# keyboard.net
KiCad netlist of a schematic drawn in Altium Designer
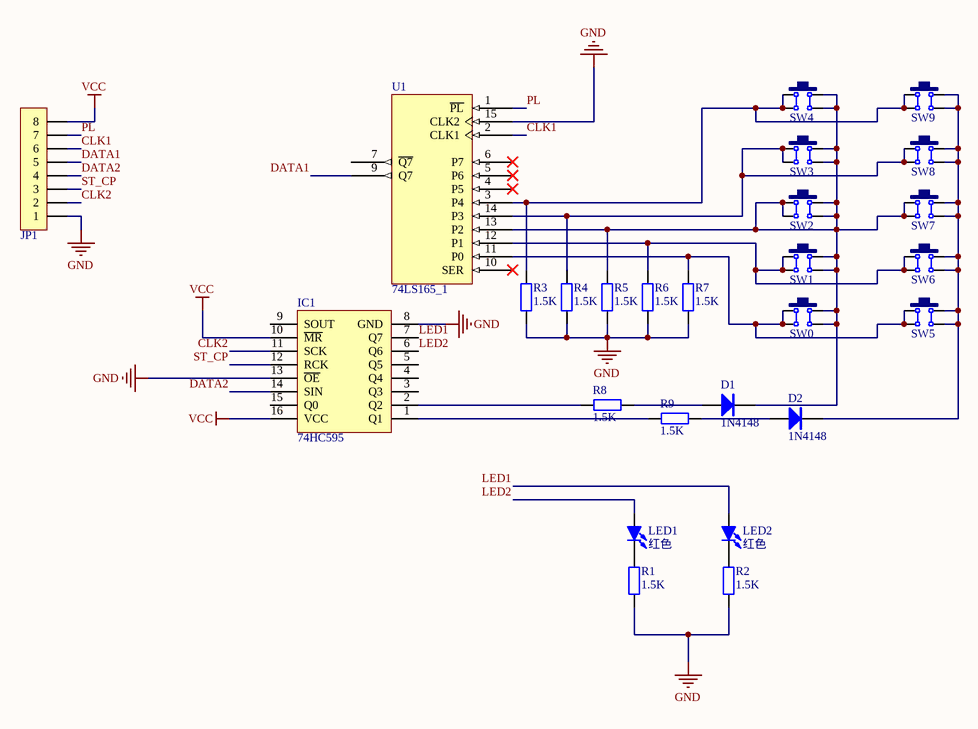
[diagram p0: keyboard.SchDoc]

(export (version "E")
  (design (tool "Eeschema 10.0.6"))
  (components
    (comp (ref "D1")
      (value "1N4148")
      (footprint "SOD-323")
      (description "高速开关二极管")
      (fields (field (name "版权归属") "源创客"))
      (libsource (lib "8.1   - 二极管-整流桥") (part "1N4148"))
    )
    (comp (ref "D2")
      (value "1N4148")
      (footprint "SOD-323")
      (description "高速开关二极管")
      (fields (field (name "版权归属") "源创客"))
      (libsource (lib "8.1   - 二极管-整流桥") (part "1N4148"))
    )
    (comp (ref "IC1")
      (value "74HC595")
      (footprint "SOP16_N")
      (description "8位移位寄存器")
      (fields (field (name "版权归属") "源创客"))
      (libsource (lib "1.2   - 74系列芯片") (part "74HC595"))
    )
    (comp (ref "JP1")
      (value "HDR-1X8")
      (footprint "XH2.54-WI-8P")
      (description "8P接插件")
      (fields (field (name "版权归属") "源创客"))
      (libsource (lib "4.5   - 接插件-脚距2.54") (part "Header 8"))
    )
    (comp (ref "LED1")
      (value "红色")
      (footprint "LED 0805R")
      (description "插件LED")
      (fields (field (name "版权归属") "源创客"))
      (libsource (lib "9.1   - LED") (part "LED-3MM"))
    )
    (comp (ref "LED2")
      (value "红色")
      (footprint "LED 0805R")
      (description "插件LED")
      (fields (field (name "版权归属") "源创客"))
      (libsource (lib "9.1   - LED") (part "LED-3MM"))
    )
    (comp (ref "R1")
      (value "1.5K")
      (footprint "R 0805_L")
      (description "贴片电阻")
      (fields (field (name "版权归属") "源创客"))
      (libsource (lib "3.1   - 电阻-电容-电感") (part "R"))
    )
    (comp (ref "R2")
      (value "1.5K")
      (footprint "R 0805_L")
      (description "贴片电阻")
      (fields (field (name "版权归属") "源创客"))
      (libsource (lib "3.1   - 电阻-电容-电感") (part "R"))
    )
    (comp (ref "R3")
      (value "1.5K")
      (footprint "R 0805_L")
      (description "贴片电阻")
      (fields (field (name "版权归属") "源创客"))
      (libsource (lib "3.1   - 电阻-电容-电感") (part "R"))
    )
    (comp (ref "R4")
      (value "1.5K")
      (footprint "R 0805_L")
      (description "贴片电阻")
      (fields (field (name "版权归属") "源创客"))
      (libsource (lib "3.1   - 电阻-电容-电感") (part "R"))
    )
    (comp (ref "R5")
      (value "1.5K")
      (footprint "R 0805_L")
      (description "贴片电阻")
      (fields (field (name "版权归属") "源创客"))
      (libsource (lib "3.1   - 电阻-电容-电感") (part "R"))
    )
    (comp (ref "R6")
      (value "1.5K")
      (footprint "R 0805_L")
      (description "贴片电阻")
      (fields (field (name "版权归属") "源创客"))
      (libsource (lib "3.1   - 电阻-电容-电感") (part "R"))
    )
    (comp (ref "R7")
      (value "1.5K")
      (footprint "R 0805_L")
      (description "贴片电阻")
      (fields (field (name "版权归属") "源创客"))
      (libsource (lib "3.1   - 电阻-电容-电感") (part "R"))
    )
    (comp (ref "R8")
      (value "1.5K")
      (footprint "R 0805_L")
      (description "贴片电阻")
      (fields (field (name "版权归属") "源创客"))
      (libsource (lib "3.1   - 电阻-电容-电感") (part "R"))
    )
    (comp (ref "R9")
      (value "1.5K")
      (footprint "R 0805_L")
      (description "贴片电阻")
      (fields (field (name "版权归属") "源创客"))
      (libsource (lib "3.1   - 电阻-电容-电感") (part "R"))
    )
    (comp (ref "SW0")
      (value "12x12x5")
      (footprint "TSW SMD-12*12*4.3")
      (description "贴片12x12轻触开关")
      (fields (field (name "版权归属") "源创客"))
      (libsource (lib "5.1   - 按键-开关") (part "TSW SMD-12x12"))
    )
    (comp (ref "SW1")
      (value "12x12x5")
      (footprint "TSW SMD-12*12*4.3")
      (description "贴片12x12轻触开关")
      (fields (field (name "版权归属") "源创客"))
      (libsource (lib "5.1   - 按键-开关") (part "TSW SMD-12x12"))
    )
    (comp (ref "SW2")
      (value "12x12x5")
      (footprint "TSW SMD-12*12*4.3")
      (description "贴片12x12轻触开关")
      (fields (field (name "版权归属") "源创客"))
      (libsource (lib "5.1   - 按键-开关") (part "TSW SMD-12x12"))
    )
    (comp (ref "SW3")
      (value "12x12x5")
      (footprint "TSW SMD-12*12*4.3")
      (description "贴片12x12轻触开关")
      (fields (field (name "版权归属") "源创客"))
      (libsource (lib "5.1   - 按键-开关") (part "TSW SMD-12x12"))
    )
    (comp (ref "SW4")
      (value "12x12x5")
      (footprint "TSW SMD-12*12*4.3")
      (description "贴片12x12轻触开关")
      (fields (field (name "版权归属") "源创客"))
      (libsource (lib "5.1   - 按键-开关") (part "TSW SMD-12x12"))
    )
    (comp (ref "SW5")
      (value "12x12x5")
      (footprint "TSW SMD-12*12*4.3")
      (description "贴片12x12轻触开关")
      (fields (field (name "版权归属") "源创客"))
      (libsource (lib "5.1   - 按键-开关") (part "TSW SMD-12x12"))
    )
    (comp (ref "SW6")
      (value "12x12x5")
      (footprint "TSW SMD-12*12*4.3")
      (description "贴片12x12轻触开关")
      (fields (field (name "版权归属") "源创客"))
      (libsource (lib "5.1   - 按键-开关") (part "TSW SMD-12x12"))
    )
    (comp (ref "SW7")
      (value "12x12x5")
      (footprint "TSW SMD-12*12*4.3")
      (description "贴片12x12轻触开关")
      (fields (field (name "版权归属") "源创客"))
      (libsource (lib "5.1   - 按键-开关") (part "TSW SMD-12x12"))
    )
    (comp (ref "SW8")
      (value "12x12x5")
      (footprint "TSW SMD-12*12*4.3")
      (description "贴片12x12轻触开关")
      (fields (field (name "版权归属") "源创客"))
      (libsource (lib "5.1   - 按键-开关") (part "TSW SMD-12x12"))
    )
    (comp (ref "SW9")
      (value "12x12x5")
      (footprint "TSW SMD-12*12*4.3")
      (description "贴片12x12轻触开关")
      (fields (field (name "版权归属") "源创客"))
      (libsource (lib "5.1   - 按键-开关") (part "TSW SMD-12x12"))
    )
    (comp (ref "U1") (value "74LS165_1") (footprint "SOP16_M") (libsource (lib "常用器件") (part "74LS165_1")))
  )
  (nets
    (net (code "1") (name "/CLK1") (class "Default")
      (node (ref "JP1") (pin "6") (pinfunction "6_6") (pintype "passive"))
      (node (ref "U1") (pin "2") (pinfunction "CLK1_2") (pintype "input"))
    )
    (net (code "2") (name "/CLK2") (class "Default")
      (node (ref "IC1") (pin "11") (pinfunction "SCK_11") (pintype "passive"))
      (node (ref "JP1") (pin "2") (pinfunction "2_2") (pintype "passive"))
    )
    (net (code "3") (name "/DATA1") (class "Default")
      (node (ref "JP1") (pin "5") (pinfunction "5_5") (pintype "passive"))
      (node (ref "U1") (pin "9") (pinfunction "Q7_9") (pintype "output"))
    )
    (net (code "4") (name "/DATA2") (class "Default")
      (node (ref "IC1") (pin "14") (pinfunction "SIN_14") (pintype "passive"))
      (node (ref "JP1") (pin "4") (pinfunction "4_4") (pintype "passive"))
    )
    (net (code "5") (name "/LED1") (class "Default")
      (node (ref "IC1") (pin "7") (pinfunction "Q7_7") (pintype "passive"))
      (node (ref "LED2") (pin "1") (pinfunction "A_1") (pintype "passive"))
    )
    (net (code "6") (name "/LED2") (class "Default")
      (node (ref "IC1") (pin "6") (pinfunction "Q6_6") (pintype "passive"))
      (node (ref "LED1") (pin "1") (pinfunction "A_1") (pintype "passive"))
    )
    (net (code "7") (name "/PL") (class "Default")
      (node (ref "JP1") (pin "7") (pinfunction "7_7") (pintype "passive"))
      (node (ref "U1") (pin "1") (pinfunction "~{PL}_1") (pintype "input"))
    )
    (net (code "8") (name "/ST_CP") (class "Default")
      (node (ref "IC1") (pin "12") (pinfunction "RCK_12") (pintype "passive"))
      (node (ref "JP1") (pin "3") (pinfunction "3_3") (pintype "passive"))
    )
    (net (code "9") (name "GND") (class "Default")
      (node (ref "IC1") (pin "13") (pinfunction "~{OE}_13") (pintype "passive"))
      (node (ref "IC1") (pin "8") (pinfunction "GND_8") (pintype "passive"))
      (node (ref "JP1") (pin "1") (pinfunction "1_1") (pintype "passive"))
      (node (ref "R1") (pin "2") (pinfunction "2_2") (pintype "passive"))
      (node (ref "R2") (pin "2") (pinfunction "2_2") (pintype "passive"))
      (node (ref "R3") (pin "2") (pinfunction "2_2") (pintype "passive"))
      (node (ref "R4") (pin "2") (pinfunction "2_2") (pintype "passive"))
      (node (ref "R5") (pin "2") (pinfunction "2_2") (pintype "passive"))
      (node (ref "R6") (pin "2") (pinfunction "2_2") (pintype "passive"))
      (node (ref "R7") (pin "2") (pinfunction "2_2") (pintype "passive"))
      (node (ref "U1") (pin "15") (pinfunction "CLK2_15") (pintype "input"))
      (node (ref "U1") (pin "8") (pinfunction "GND_8") (pintype "power_in"))
    )
    (net (code "10") (name "Net-(D1-A)") (class "Default")
      (node (ref "D1") (pin "1") (pinfunction "A_1") (pintype "passive"))
      (node (ref "R8") (pin "2") (pinfunction "2_2") (pintype "passive"))
    )
    (net (code "11") (name "Net-(D1-K)") (class "Default")
      (node (ref "D1") (pin "2") (pinfunction "K_2") (pintype "passive"))
      (node (ref "R5") (pin "1") (pinfunction "1_1") (pintype "passive"))
      (node (ref "SW0") (pin "2") (pinfunction "2_2") (pintype "passive"))
      (node (ref "SW0") (pin "3") (pinfunction "3_3") (pintype "passive"))
      (node (ref "SW1") (pin "2") (pinfunction "2_2") (pintype "passive"))
      (node (ref "SW1") (pin "3") (pinfunction "3_3") (pintype "passive"))
      (node (ref "SW2") (pin "1") (pinfunction "1_1") (pintype "passive"))
      (node (ref "SW2") (pin "2") (pinfunction "2_2") (pintype "passive"))
      (node (ref "SW2") (pin "3") (pinfunction "3_3") (pintype "passive"))
      (node (ref "SW2") (pin "4") (pinfunction "4_4") (pintype "passive"))
      (node (ref "SW3") (pin "2") (pinfunction "2_2") (pintype "passive"))
      (node (ref "SW3") (pin "3") (pinfunction "3_3") (pintype "passive"))
      (node (ref "SW4") (pin "2") (pinfunction "2_2") (pintype "passive"))
      (node (ref "SW4") (pin "3") (pinfunction "3_3") (pintype "passive"))
      (node (ref "SW7") (pin "1") (pinfunction "1_1") (pintype "passive"))
      (node (ref "SW7") (pin "4") (pinfunction "4_4") (pintype "passive"))
      (node (ref "U1") (pin "13") (pinfunction "P2_13") (pintype "input"))
    )
    (net (code "12") (name "Net-(D2-A)") (class "Default")
      (node (ref "D2") (pin "1") (pinfunction "A_1") (pintype "passive"))
      (node (ref "R9") (pin "2") (pinfunction "2_2") (pintype "passive"))
    )
    (net (code "13") (name "Net-(D2-K)") (class "Default")
      (node (ref "D2") (pin "2") (pinfunction "K_2") (pintype "passive"))
      (node (ref "SW5") (pin "2") (pinfunction "2_2") (pintype "passive"))
      (node (ref "SW5") (pin "3") (pinfunction "3_3") (pintype "passive"))
      (node (ref "SW6") (pin "2") (pinfunction "2_2") (pintype "passive"))
      (node (ref "SW6") (pin "3") (pinfunction "3_3") (pintype "passive"))
      (node (ref "SW7") (pin "2") (pinfunction "2_2") (pintype "passive"))
      (node (ref "SW7") (pin "3") (pinfunction "3_3") (pintype "passive"))
      (node (ref "SW8") (pin "2") (pinfunction "2_2") (pintype "passive"))
      (node (ref "SW8") (pin "3") (pinfunction "3_3") (pintype "passive"))
      (node (ref "SW9") (pin "2") (pinfunction "2_2") (pintype "passive"))
      (node (ref "SW9") (pin "3") (pinfunction "3_3") (pintype "passive"))
    )
    (net (code "14") (name "Net-(IC1-Q1)") (class "Default")
      (node (ref "IC1") (pin "1") (pinfunction "Q1_1") (pintype "passive"))
      (node (ref "R9") (pin "1") (pinfunction "1_1") (pintype "passive"))
    )
    (net (code "15") (name "Net-(IC1-Q2)") (class "Default")
      (node (ref "IC1") (pin "2") (pinfunction "Q2_2") (pintype "passive"))
      (node (ref "R8") (pin "1") (pinfunction "1_1") (pintype "passive"))
    )
    (net (code "16") (name "Net-(LED1-K)") (class "Default")
      (node (ref "LED1") (pin "2") (pinfunction "K_2") (pintype "passive"))
      (node (ref "R1") (pin "1") (pinfunction "1_1") (pintype "passive"))
    )
    (net (code "17") (name "Net-(LED2-K)") (class "Default")
      (node (ref "LED2") (pin "2") (pinfunction "K_2") (pintype "passive"))
      (node (ref "R2") (pin "1") (pinfunction "1_1") (pintype "passive"))
    )
    (net (code "18") (name "Net-(U1-P0)") (class "Default")
      (node (ref "R7") (pin "1") (pinfunction "1_1") (pintype "passive"))
      (node (ref "SW0") (pin "1") (pinfunction "1_1") (pintype "passive"))
      (node (ref "SW0") (pin "4") (pinfunction "4_4") (pintype "passive"))
      (node (ref "SW5") (pin "1") (pinfunction "1_1") (pintype "passive"))
      (node (ref "SW5") (pin "4") (pinfunction "4_4") (pintype "passive"))
      (node (ref "U1") (pin "11") (pinfunction "P0_11") (pintype "input"))
    )
    (net (code "19") (name "Net-(U1-P1)") (class "Default")
      (node (ref "R6") (pin "1") (pinfunction "1_1") (pintype "passive"))
      (node (ref "SW1") (pin "1") (pinfunction "1_1") (pintype "passive"))
      (node (ref "SW1") (pin "4") (pinfunction "4_4") (pintype "passive"))
      (node (ref "SW6") (pin "1") (pinfunction "1_1") (pintype "passive"))
      (node (ref "SW6") (pin "4") (pinfunction "4_4") (pintype "passive"))
      (node (ref "U1") (pin "12") (pinfunction "P1_12") (pintype "input"))
    )
    (net (code "20") (name "Net-(U1-P3)") (class "Default")
      (node (ref "R4") (pin "1") (pinfunction "1_1") (pintype "passive"))
      (node (ref "SW3") (pin "1") (pinfunction "1_1") (pintype "passive"))
      (node (ref "SW3") (pin "4") (pinfunction "4_4") (pintype "passive"))
      (node (ref "SW8") (pin "1") (pinfunction "1_1") (pintype "passive"))
      (node (ref "SW8") (pin "4") (pinfunction "4_4") (pintype "passive"))
      (node (ref "U1") (pin "14") (pinfunction "P3_14") (pintype "input"))
    )
    (net (code "21") (name "Net-(U1-P4)") (class "Default")
      (node (ref "R3") (pin "1") (pinfunction "1_1") (pintype "passive"))
      (node (ref "SW4") (pin "1") (pinfunction "1_1") (pintype "passive"))
      (node (ref "SW4") (pin "4") (pinfunction "4_4") (pintype "passive"))
      (node (ref "SW9") (pin "1") (pinfunction "1_1") (pintype "passive"))
      (node (ref "SW9") (pin "4") (pinfunction "4_4") (pintype "passive"))
      (node (ref "U1") (pin "3") (pinfunction "P4_3") (pintype "input"))
    )
    (net (code "22") (name "VCC") (class "Default")
      (node (ref "IC1") (pin "10") (pinfunction "~{MR}_10") (pintype "passive"))
      (node (ref "IC1") (pin "16") (pinfunction "VCC_16") (pintype "passive"))
      (node (ref "JP1") (pin "8") (pinfunction "8_8") (pintype "passive"))
      (node (ref "U1") (pin "16") (pinfunction "VCC_16") (pintype "power_in"))
    )
    (net (code "23") (name "unconnected-(IC1-Q0-Pad15)") (class "Default")
      (node (ref "IC1") (pin "15") (pinfunction "Q0_15") (pintype "passive"))
    )
    (net (code "24") (name "unconnected-(IC1-Q3-Pad3)") (class "Default")
      (node (ref "IC1") (pin "3") (pinfunction "Q3_3") (pintype "passive"))
    )
    (net (code "25") (name "unconnected-(IC1-Q4-Pad4)") (class "Default")
      (node (ref "IC1") (pin "4") (pinfunction "Q4_4") (pintype "passive"))
    )
    (net (code "26") (name "unconnected-(IC1-Q5-Pad5)") (class "Default")
      (node (ref "IC1") (pin "5") (pinfunction "Q5_5") (pintype "passive"))
    )
    (net (code "27") (name "unconnected-(IC1-SOUT-Pad9)") (class "Default")
      (node (ref "IC1") (pin "9") (pinfunction "SOUT_9") (pintype "passive"))
    )
    (net (code "28") (name "unconnected-(U1-P5-Pad4)") (class "Default")
      (node (ref "U1") (pin "4") (pinfunction "P5_4") (pintype "input+no_connect"))
    )
    (net (code "29") (name "unconnected-(U1-P6-Pad5)") (class "Default")
      (node (ref "U1") (pin "5") (pinfunction "P6_5") (pintype "input+no_connect"))
    )
    (net (code "30") (name "unconnected-(U1-P7-Pad6)") (class "Default")
      (node (ref "U1") (pin "6") (pinfunction "P7_6") (pintype "input+no_connect"))
    )
    (net (code "31") (name "unconnected-(U1-SER-Pad10)") (class "Default")
      (node (ref "U1") (pin "10") (pinfunction "SER_10") (pintype "input+no_connect"))
    )
    (net (code "32") (name "unconnected-(U1-~{Q7}-Pad7)") (class "Default")
      (node (ref "U1") (pin "7") (pinfunction "~{Q7}_7") (pintype "output"))
    )
  )
)
